# schematic.net
KiCad netlist of a schematic drawn in EasyEDA
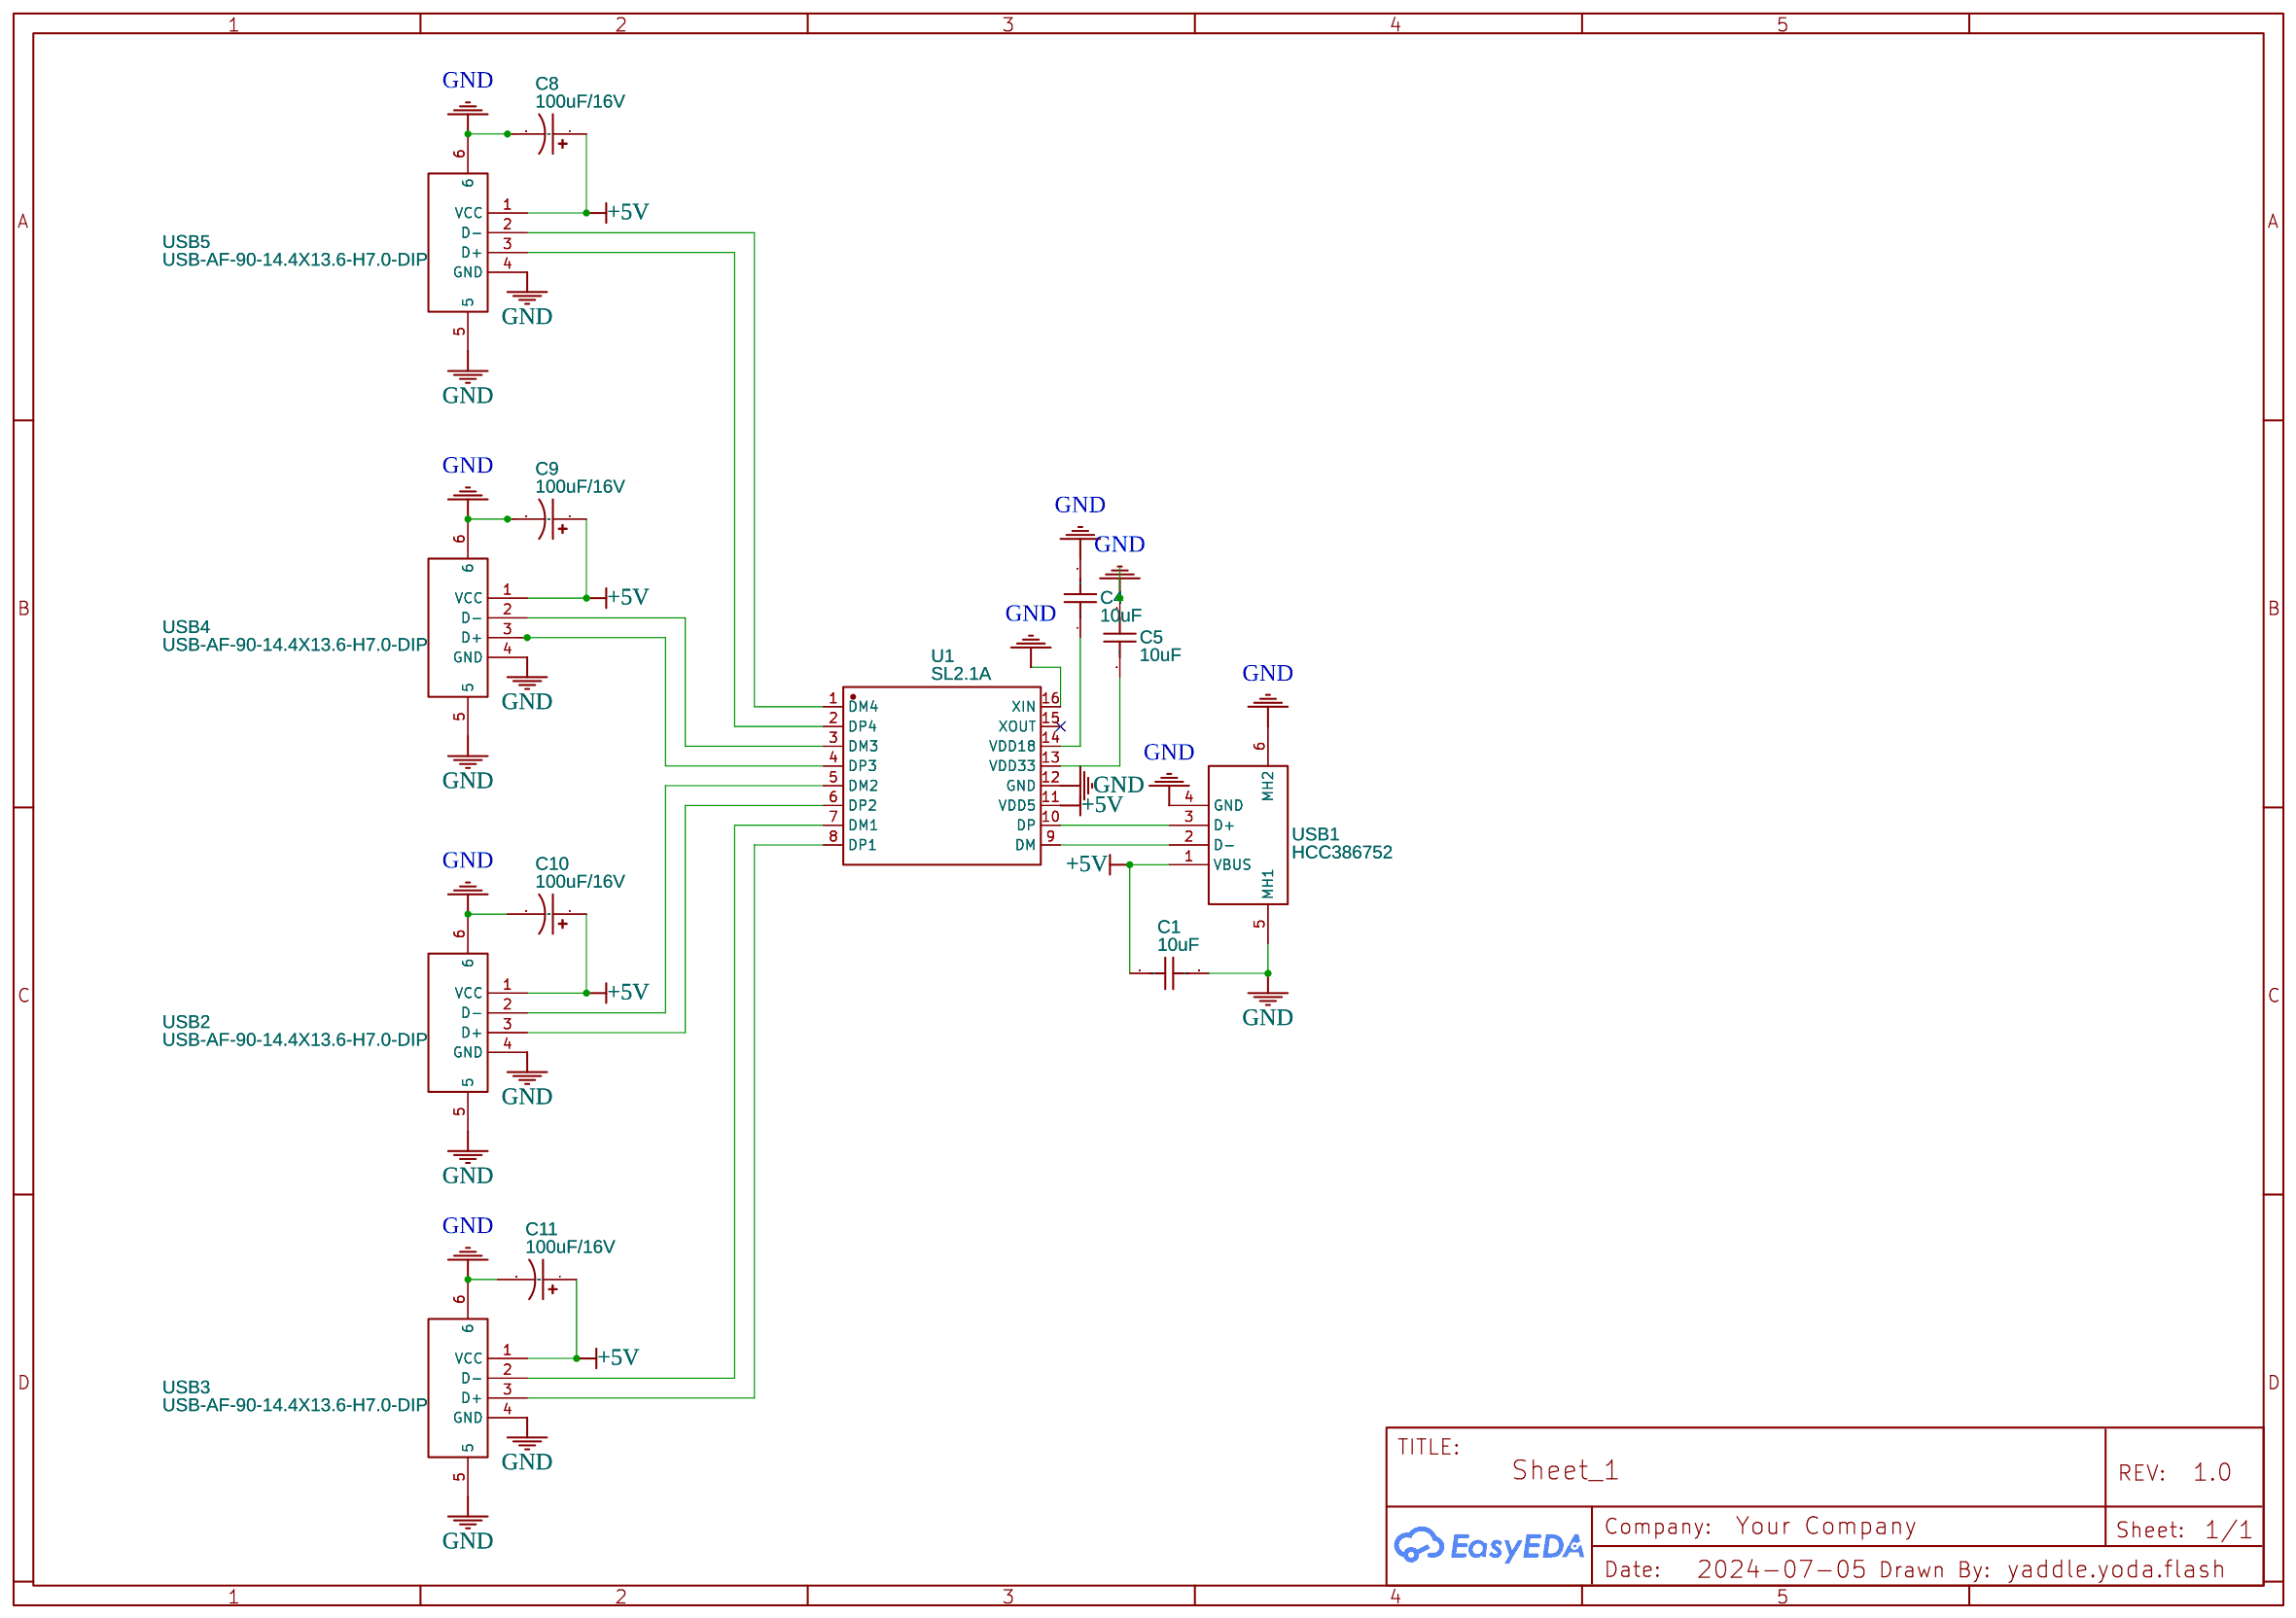
[diagram p0: Horizontal_USB]
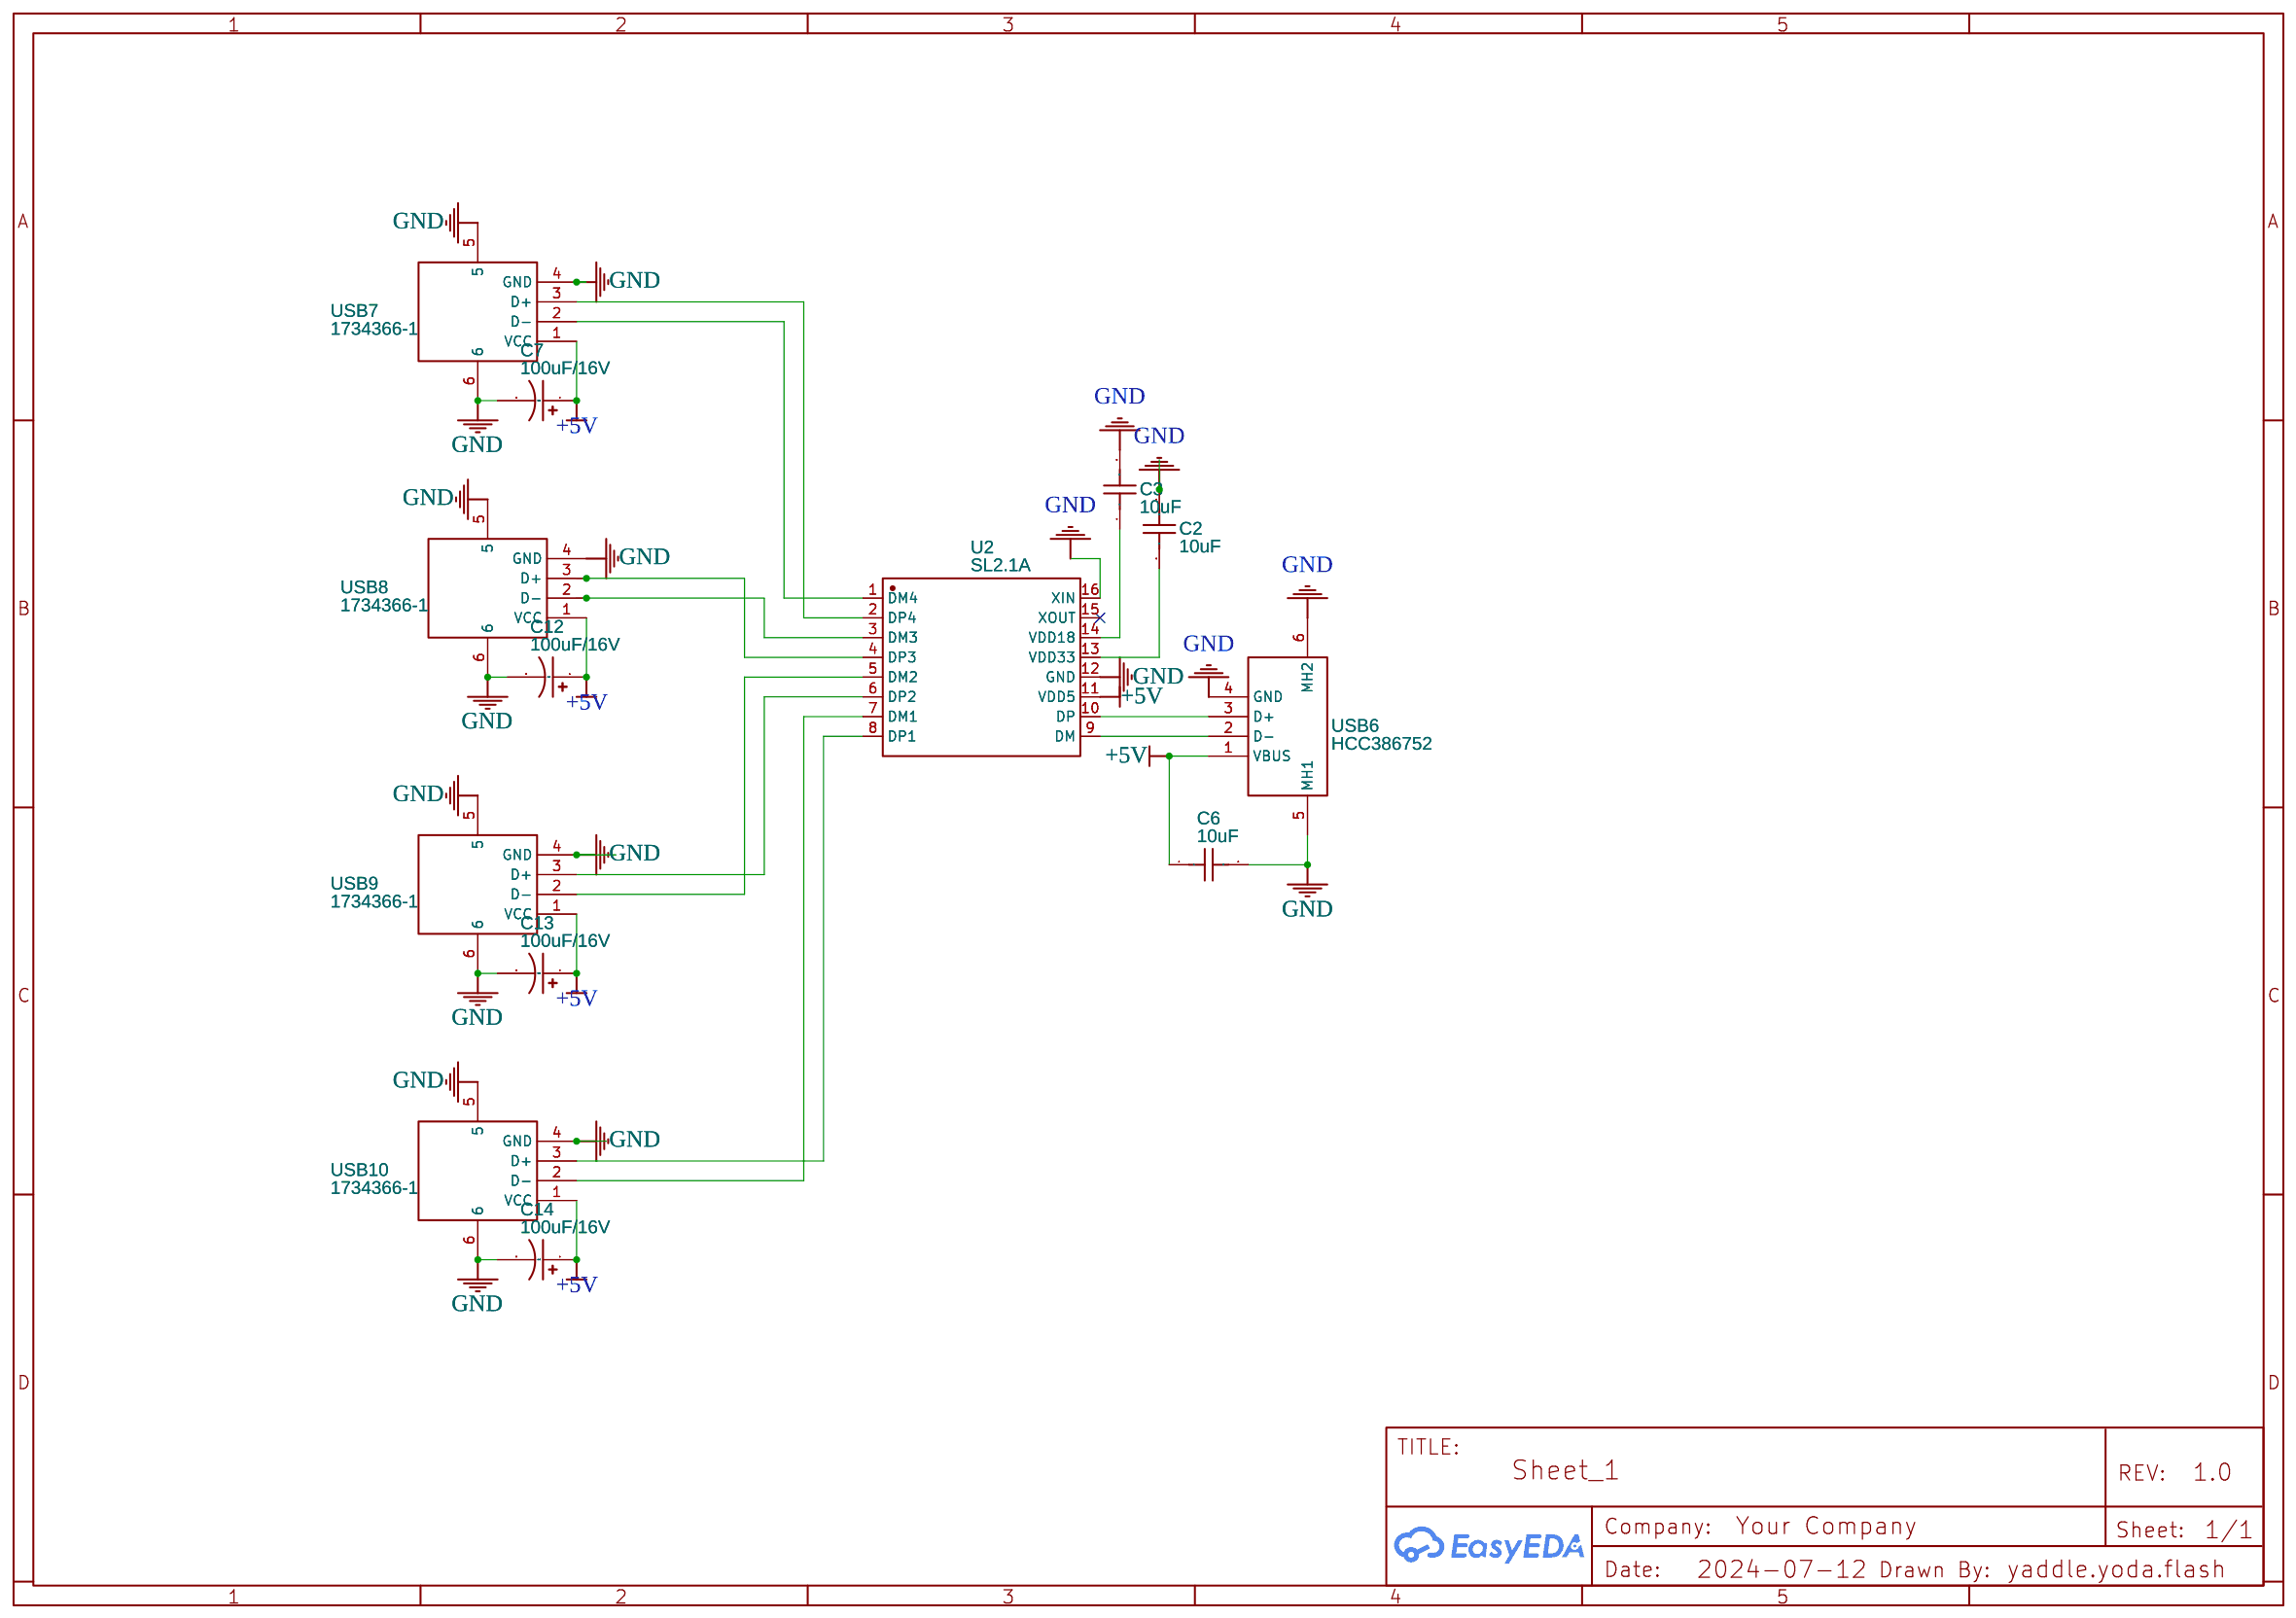
[diagram p1: Vertical_USB]

(export (version "E")
  (design (tool "Eeschema 10.0.6"))
  (components
    (comp (ref "C1")
      (value "10uF")
      (fields
        (field (name "Manufacturer Part") "CL10A106KP8NNNC")
        (field (name "Manufacturer") "SAMSUNG(三星)")
      )
      (libsource (lib "") (part "CL10A106KP8NNNC"))
    )
    (comp (ref "C4")
      (value "10uF")
      (fields
        (field (name "Manufacturer Part") "CL10A106KP8NNNC")
        (field (name "Manufacturer") "SAMSUNG(三星)")
      )
      (libsource (lib "") (part "CL10A106KP8NNNC_1"))
    )
    (comp (ref "C5")
      (value "10uF")
      (fields
        (field (name "Manufacturer Part") "CL10A106KP8NNNC")
        (field (name "Manufacturer") "SAMSUNG(三星)")
      )
      (libsource (lib "") (part "CL10A106KP8NNNC_2"))
    )
    (comp (ref "C8") (value "100uF/16V") (libsource (lib "") (part "C_Tan_SMD_A_US")))
    (comp (ref "C9") (value "100uF/16V") (libsource (lib "") (part "C_Tan_SMD_A_US")))
    (comp (ref "C10") (value "100uF/16V") (libsource (lib "") (part "C_Tan_SMD_A_US")))
    (comp (ref "C11") (value "100uF/16V") (libsource (lib "") (part "C_Tan_SMD_A_US_1")))
    (comp (ref "U1")
      (value "SL2.1A")
      (fields (field (name "Manufacturer") "CoreChips(和芯润德)"))
      (libsource (lib "") (part "SL2.1A"))
    )
    (comp (ref "USB1")
      (value "HCC386752")
      (fields (field (name "Manufacturer Part") "U-USBAR04P-M003") (field (name "Manufacturer") "Ckmtw(灿科盟)"))
      (libsource (lib "") (part "HCC386752"))
    )
    (comp (ref "USB2")
      (value "USB-AF-90-14.4X13.6-H7.0-DIP")
      (fields (field (name "Manufacturer Part") "903-131A1011D10100") (field (name "Manufacturer") "精拓金"))
      (libsource (lib "") (part "USB-AF-90-14.4X13.6-H7.0-DIP"))
    )
    (comp (ref "USB3")
      (value "USB-AF-90-14.4X13.6-H7.0-DIP")
      (fields (field (name "Manufacturer Part") "903-131A1011D10100") (field (name "Manufacturer") "精拓金"))
      (libsource (lib "") (part "USB-AF-90-14.4X13.6-H7.0-DIP"))
    )
    (comp (ref "USB4")
      (value "USB-AF-90-14.4X13.6-H7.0-DIP")
      (fields (field (name "Manufacturer Part") "903-131A1011D10100") (field (name "Manufacturer") "精拓金"))
      (libsource (lib "") (part "USB-AF-90-14.4X13.6-H7.0-DIP"))
    )
    (comp (ref "USB5")
      (value "USB-AF-90-14.4X13.6-H7.0-DIP")
      (fields (field (name "Manufacturer Part") "903-131A1011D10100") (field (name "Manufacturer") "精拓金"))
      (libsource (lib "") (part "USB-AF-90-14.4X13.6-H7.0-DIP"))
    )
    (comp (ref "C2")
      (value "10uF")
      (fields
        (field (name "Manufacturer Part") "CL10A106KP8NNNC")
        (field (name "Manufacturer") "SAMSUNG(三星)")
      )
      (libsource (lib "") (part "CL10A106KP8NNNC_1"))
    )
    (comp (ref "C3")
      (value "10uF")
      (fields
        (field (name "Manufacturer Part") "CL10A106KP8NNNC")
        (field (name "Manufacturer") "SAMSUNG(三星)")
      )
      (libsource (lib "") (part "CL10A106KP8NNNC"))
    )
    (comp (ref "C6")
      (value "10uF")
      (fields
        (field (name "Manufacturer Part") "CL10A106KP8NNNC")
        (field (name "Manufacturer") "SAMSUNG(三星)")
      )
      (libsource (lib "") (part "CL10A106KP8NNNC_2"))
    )
    (comp (ref "C7") (value "100uF/16V") (libsource (lib "") (part "C_Tan_SMD_A_US")))
    (comp (ref "C12") (value "100uF/16V") (libsource (lib "") (part "C_Tan_SMD_A_US")))
    (comp (ref "C13") (value "100uF/16V") (libsource (lib "") (part "C_Tan_SMD_A_US")))
    (comp (ref "C14") (value "100uF/16V") (libsource (lib "") (part "C_Tan_SMD_A_US_1")))
    (comp (ref "U2")
      (value "SL2.1A")
      (fields (field (name "Manufacturer") "CoreChips(和芯润德)"))
      (libsource (lib "") (part "SL2.1A"))
    )
    (comp (ref "USB6")
      (value "HCC386752")
      (fields (field (name "Manufacturer Part") "U-USBAR04P-M003") (field (name "Manufacturer") "Ckmtw(灿科盟)"))
      (libsource (lib "") (part "HCC386752"))
    )
    (comp (ref "USB7")
      (value "1734366-1")
      (fields (field (name "Manufacturer") "TE Connectivity(泰科电子)"))
      (libsource (lib "") (part "1734366-1"))
    )
    (comp (ref "USB8")
      (value "1734366-1")
      (fields (field (name "Manufacturer") "TE Connectivity(泰科电子)"))
      (libsource (lib "") (part "1734366-1"))
    )
    (comp (ref "USB9")
      (value "1734366-1")
      (fields (field (name "Manufacturer") "TE Connectivity(泰科电子)"))
      (libsource (lib "") (part "1734366-1"))
    )
    (comp (ref "USB10")
      (value "1734366-1")
      (fields (field (name "Manufacturer") "TE Connectivity(泰科电子)"))
      (libsource (lib "") (part "1734366-1"))
    )
  )
  (nets
    (net (code "1") (name "+5V") (class "Default")
      (node (ref "C1") (pin "1") (pinfunction "1_1") (pintype "unspecified"))
      (node (ref "C10") (pin "1") (pinfunction "1_1") (pintype "unspecified"))
      (node (ref "C11") (pin "1") (pinfunction "1_1") (pintype "unspecified"))
      (node (ref "C12") (pin "1") (pinfunction "1_1") (pintype "unspecified"))
      (node (ref "C13") (pin "1") (pinfunction "1_1") (pintype "unspecified"))
      (node (ref "C14") (pin "1") (pinfunction "1_1") (pintype "unspecified"))
      (node (ref "C6") (pin "1") (pinfunction "1_1") (pintype "unspecified"))
      (node (ref "C7") (pin "1") (pinfunction "1_1") (pintype "unspecified"))
      (node (ref "C8") (pin "1") (pinfunction "1_1") (pintype "unspecified"))
      (node (ref "C9") (pin "1") (pinfunction "1_1") (pintype "unspecified"))
      (node (ref "U1") (pin "11") (pinfunction "VDD5_11") (pintype "unspecified"))
      (node (ref "U2") (pin "11") (pinfunction "VDD5_11") (pintype "unspecified"))
      (node (ref "USB1") (pin "1") (pinfunction "VBUS_1") (pintype "unspecified"))
      (node (ref "USB10") (pin "1") (pinfunction "VCC_1") (pintype "unspecified"))
      (node (ref "USB2") (pin "1") (pinfunction "VCC_1") (pintype "unspecified"))
      (node (ref "USB3") (pin "1") (pinfunction "VCC_1") (pintype "unspecified"))
      (node (ref "USB4") (pin "1") (pinfunction "VCC_1") (pintype "unspecified"))
      (node (ref "USB5") (pin "1") (pinfunction "VCC_1") (pintype "unspecified"))
      (node (ref "USB6") (pin "1") (pinfunction "VBUS_1") (pintype "unspecified"))
      (node (ref "USB7") (pin "1") (pinfunction "VCC_1") (pintype "unspecified"))
      (node (ref "USB8") (pin "1") (pinfunction "VCC_1") (pintype "unspecified"))
      (node (ref "USB9") (pin "1") (pinfunction "VCC_1") (pintype "unspecified"))
    )
    (net (code "2") (name "GND") (class "Default")
      (node (ref "C1") (pin "2") (pinfunction "2_2") (pintype "unspecified"))
      (node (ref "C10") (pin "2") (pinfunction "2_2") (pintype "unspecified"))
      (node (ref "C11") (pin "2") (pinfunction "2_2") (pintype "unspecified"))
      (node (ref "C12") (pin "2") (pinfunction "2_2") (pintype "unspecified"))
      (node (ref "C13") (pin "2") (pinfunction "2_2") (pintype "unspecified"))
      (node (ref "C14") (pin "2") (pinfunction "2_2") (pintype "unspecified"))
      (node (ref "C2") (pin "1") (pinfunction "1_1") (pintype "unspecified"))
      (node (ref "C3") (pin "2") (pinfunction "2_2") (pintype "unspecified"))
      (node (ref "C4") (pin "2") (pinfunction "2_2") (pintype "unspecified"))
      (node (ref "C5") (pin "1") (pinfunction "1_1") (pintype "unspecified"))
      (node (ref "C6") (pin "2") (pinfunction "2_2") (pintype "unspecified"))
      (node (ref "C7") (pin "2") (pinfunction "2_2") (pintype "unspecified"))
      (node (ref "C8") (pin "2") (pinfunction "2_2") (pintype "unspecified"))
      (node (ref "C9") (pin "2") (pinfunction "2_2") (pintype "unspecified"))
      (node (ref "U1") (pin "12") (pinfunction "GND_12") (pintype "unspecified"))
      (node (ref "U1") (pin "16") (pinfunction "XIN_16") (pintype "unspecified"))
      (node (ref "U2") (pin "12") (pinfunction "GND_12") (pintype "unspecified"))
      (node (ref "U2") (pin "16") (pinfunction "XIN_16") (pintype "unspecified"))
      (node (ref "USB1") (pin "4") (pinfunction "GND_4") (pintype "unspecified"))
      (node (ref "USB1") (pin "5") (pinfunction "MH1_5") (pintype "unspecified"))
      (node (ref "USB1") (pin "6") (pinfunction "MH2_6") (pintype "unspecified"))
      (node (ref "USB10") (pin "4") (pinfunction "GND_4") (pintype "unspecified"))
      (node (ref "USB10") (pin "5") (pinfunction "5_5") (pintype "unspecified"))
      (node (ref "USB10") (pin "6") (pinfunction "6_6") (pintype "unspecified"))
      (node (ref "USB2") (pin "4") (pinfunction "GND_4") (pintype "unspecified"))
      (node (ref "USB2") (pin "5") (pinfunction "5_5") (pintype "unspecified"))
      (node (ref "USB2") (pin "6") (pinfunction "6_6") (pintype "unspecified"))
      (node (ref "USB3") (pin "4") (pinfunction "GND_4") (pintype "unspecified"))
      (node (ref "USB3") (pin "5") (pinfunction "5_5") (pintype "unspecified"))
      (node (ref "USB3") (pin "6") (pinfunction "6_6") (pintype "unspecified"))
      (node (ref "USB4") (pin "4") (pinfunction "GND_4") (pintype "unspecified"))
      (node (ref "USB4") (pin "5") (pinfunction "5_5") (pintype "unspecified"))
      (node (ref "USB4") (pin "6") (pinfunction "6_6") (pintype "unspecified"))
      (node (ref "USB5") (pin "4") (pinfunction "GND_4") (pintype "unspecified"))
      (node (ref "USB5") (pin "5") (pinfunction "5_5") (pintype "unspecified"))
      (node (ref "USB5") (pin "6") (pinfunction "6_6") (pintype "unspecified"))
      (node (ref "USB6") (pin "4") (pinfunction "GND_4") (pintype "unspecified"))
      (node (ref "USB6") (pin "5") (pinfunction "MH1_5") (pintype "unspecified"))
      (node (ref "USB6") (pin "6") (pinfunction "MH2_6") (pintype "unspecified"))
      (node (ref "USB7") (pin "4") (pinfunction "GND_4") (pintype "unspecified"))
      (node (ref "USB7") (pin "5") (pinfunction "5_5") (pintype "unspecified"))
      (node (ref "USB7") (pin "6") (pinfunction "6_6") (pintype "unspecified"))
      (node (ref "USB8") (pin "4") (pinfunction "GND_4") (pintype "unspecified"))
      (node (ref "USB8") (pin "5") (pinfunction "5_5") (pintype "unspecified"))
      (node (ref "USB8") (pin "6") (pinfunction "6_6") (pintype "unspecified"))
      (node (ref "USB9") (pin "4") (pinfunction "GND_4") (pintype "unspecified"))
      (node (ref "USB9") (pin "5") (pinfunction "5_5") (pintype "unspecified"))
      (node (ref "USB9") (pin "6") (pinfunction "6_6") (pintype "unspecified"))
    )
    (net (code "3") (name "Net-(U1-DM)") (class "Default")
      (node (ref "U1") (pin "9") (pinfunction "DM_9") (pintype "unspecified"))
      (node (ref "USB1") (pin "2") (pinfunction "D-_2") (pintype "unspecified"))
    )
    (net (code "4") (name "Net-(U1-DM1)") (class "Default")
      (node (ref "U1") (pin "7") (pinfunction "DM1_7") (pintype "unspecified"))
      (node (ref "USB3") (pin "2") (pinfunction "D-_2") (pintype "unspecified"))
    )
    (net (code "5") (name "Net-(U1-DM2)") (class "Default")
      (node (ref "U1") (pin "5") (pinfunction "DM2_5") (pintype "unspecified"))
      (node (ref "USB2") (pin "2") (pinfunction "D-_2") (pintype "unspecified"))
    )
    (net (code "6") (name "Net-(U1-DM3)") (class "Default")
      (node (ref "U1") (pin "3") (pinfunction "DM3_3") (pintype "unspecified"))
      (node (ref "USB4") (pin "2") (pinfunction "D-_2") (pintype "unspecified"))
    )
    (net (code "7") (name "Net-(U1-DM4)") (class "Default")
      (node (ref "U1") (pin "1") (pinfunction "DM4_1") (pintype "unspecified"))
      (node (ref "USB5") (pin "2") (pinfunction "D-_2") (pintype "unspecified"))
    )
    (net (code "8") (name "Net-(U1-DP)") (class "Default")
      (node (ref "U1") (pin "10") (pinfunction "DP_10") (pintype "unspecified"))
      (node (ref "USB1") (pin "3") (pinfunction "D+_3") (pintype "unspecified"))
    )
    (net (code "9") (name "Net-(U1-DP1)") (class "Default")
      (node (ref "U1") (pin "8") (pinfunction "DP1_8") (pintype "unspecified"))
      (node (ref "USB3") (pin "3") (pinfunction "D+_3") (pintype "unspecified"))
    )
    (net (code "10") (name "Net-(U1-DP2)") (class "Default")
      (node (ref "U1") (pin "6") (pinfunction "DP2_6") (pintype "unspecified"))
      (node (ref "USB2") (pin "3") (pinfunction "D+_3") (pintype "unspecified"))
    )
    (net (code "11") (name "Net-(U1-DP3)") (class "Default")
      (node (ref "U1") (pin "4") (pinfunction "DP3_4") (pintype "unspecified"))
      (node (ref "USB4") (pin "3") (pinfunction "D+_3") (pintype "unspecified"))
    )
    (net (code "12") (name "Net-(U1-DP4)") (class "Default")
      (node (ref "U1") (pin "2") (pinfunction "DP4_2") (pintype "unspecified"))
      (node (ref "USB5") (pin "3") (pinfunction "D+_3") (pintype "unspecified"))
    )
    (net (code "13") (name "Net-(U1-VDD18)") (class "Default")
      (node (ref "C4") (pin "1") (pinfunction "1_1") (pintype "unspecified"))
      (node (ref "U1") (pin "14") (pinfunction "VDD18_14") (pintype "unspecified"))
    )
    (net (code "14") (name "Net-(U1-VDD33)") (class "Default")
      (node (ref "C5") (pin "2") (pinfunction "2_2") (pintype "unspecified"))
      (node (ref "U1") (pin "13") (pinfunction "VDD33_13") (pintype "unspecified"))
    )
    (net (code "15") (name "Net-(U2-DM)") (class "Default")
      (node (ref "U2") (pin "9") (pinfunction "DM_9") (pintype "unspecified"))
      (node (ref "USB6") (pin "2") (pinfunction "D-_2") (pintype "unspecified"))
    )
    (net (code "16") (name "Net-(U2-DM1)") (class "Default")
      (node (ref "U2") (pin "7") (pinfunction "DM1_7") (pintype "unspecified"))
      (node (ref "USB10") (pin "2") (pinfunction "D-_2") (pintype "unspecified"))
    )
    (net (code "17") (name "Net-(U2-DM2)") (class "Default")
      (node (ref "U2") (pin "5") (pinfunction "DM2_5") (pintype "unspecified"))
      (node (ref "USB9") (pin "2") (pinfunction "D-_2") (pintype "unspecified"))
    )
    (net (code "18") (name "Net-(U2-DM3)") (class "Default")
      (node (ref "U2") (pin "3") (pinfunction "DM3_3") (pintype "unspecified"))
      (node (ref "USB8") (pin "2") (pinfunction "D-_2") (pintype "unspecified"))
    )
    (net (code "19") (name "Net-(U2-DM4)") (class "Default")
      (node (ref "U2") (pin "1") (pinfunction "DM4_1") (pintype "unspecified"))
      (node (ref "USB7") (pin "2") (pinfunction "D-_2") (pintype "unspecified"))
    )
    (net (code "20") (name "Net-(U2-DP)") (class "Default")
      (node (ref "U2") (pin "10") (pinfunction "DP_10") (pintype "unspecified"))
      (node (ref "USB6") (pin "3") (pinfunction "D+_3") (pintype "unspecified"))
    )
    (net (code "21") (name "Net-(U2-DP1)") (class "Default")
      (node (ref "U2") (pin "8") (pinfunction "DP1_8") (pintype "unspecified"))
      (node (ref "USB10") (pin "3") (pinfunction "D+_3") (pintype "unspecified"))
    )
    (net (code "22") (name "Net-(U2-DP2)") (class "Default")
      (node (ref "U2") (pin "6") (pinfunction "DP2_6") (pintype "unspecified"))
      (node (ref "USB9") (pin "3") (pinfunction "D+_3") (pintype "unspecified"))
    )
    (net (code "23") (name "Net-(U2-DP3)") (class "Default")
      (node (ref "U2") (pin "4") (pinfunction "DP3_4") (pintype "unspecified"))
      (node (ref "USB8") (pin "3") (pinfunction "D+_3") (pintype "unspecified"))
    )
    (net (code "24") (name "Net-(U2-DP4)") (class "Default")
      (node (ref "U2") (pin "2") (pinfunction "DP4_2") (pintype "unspecified"))
      (node (ref "USB7") (pin "3") (pinfunction "D+_3") (pintype "unspecified"))
    )
    (net (code "25") (name "Net-(U2-VDD18)") (class "Default")
      (node (ref "C3") (pin "1") (pinfunction "1_1") (pintype "unspecified"))
      (node (ref "U2") (pin "14") (pinfunction "VDD18_14") (pintype "unspecified"))
    )
    (net (code "26") (name "Net-(U2-VDD33)") (class "Default")
      (node (ref "C2") (pin "2") (pinfunction "2_2") (pintype "unspecified"))
      (node (ref "U2") (pin "13") (pinfunction "VDD33_13") (pintype "unspecified"))
    )
    (net (code "27") (name "unconnected-(U1-XOUT-Pad15)") (class "Default")
      (node (ref "U1") (pin "15") (pinfunction "XOUT_15") (pintype "unspecified+no_connect"))
    )
    (net (code "28") (name "unconnected-(U2-XOUT-Pad15)") (class "Default")
      (node (ref "U2") (pin "15") (pinfunction "XOUT_15") (pintype "unspecified+no_connect"))
    )
  )
)
